# guitar_pedal_adapter.net
KiCad netlist of a schematic drawn in EAGLE
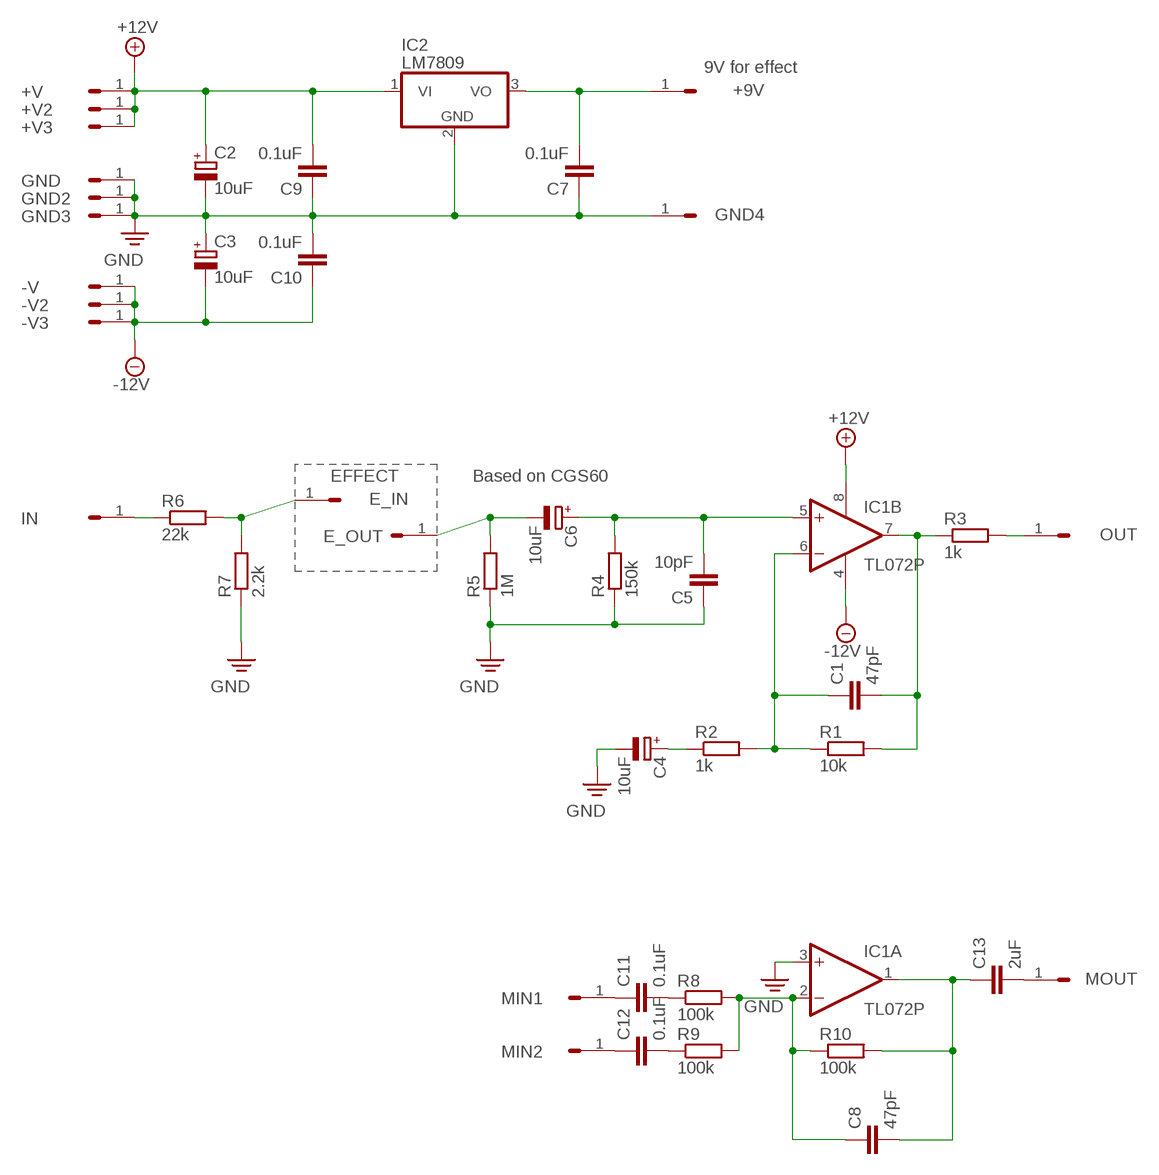
[diagram p0: schematic, sheet 1]

(export (version "E")
  (design (tool "Eeschema 10.0.6"))
  (components
    (comp (ref "+9V")
      (value "HEADER/MALE/01")
      (footprint "eagle-import:HEADER_MALE_01")
      (fields (field (name "SPICEPREFIX") "X"))
      (libsource (lib "eagle-import") (part "HEADER/MALE/01"))
    )
    (comp (ref "+V")
      (value "HEADER/MALE/01")
      (footprint "eagle-import:HEADER_MALE_01")
      (fields (field (name "SPICEPREFIX") "X"))
      (libsource (lib "eagle-import") (part "HEADER/MALE/01"))
    )
    (comp (ref "+V2")
      (value "HEADER/MALE/01")
      (footprint "eagle-import:HEADER_MALE_01")
      (fields (field (name "SPICEPREFIX") "X"))
      (libsource (lib "eagle-import") (part "HEADER/MALE/01"))
    )
    (comp (ref "+V3")
      (value "HEADER/MALE/01")
      (footprint "eagle-import:HEADER_MALE_01")
      (fields (field (name "SPICEPREFIX") "X"))
      (libsource (lib "eagle-import") (part "HEADER/MALE/01"))
    )
    (comp (ref "-V")
      (value "HEADER/MALE/01")
      (footprint "eagle-import:HEADER_MALE_01")
      (fields (field (name "SPICEPREFIX") "X"))
      (libsource (lib "eagle-import") (part "HEADER/MALE/01"))
    )
    (comp (ref "-V2")
      (value "HEADER/MALE/01")
      (footprint "eagle-import:HEADER_MALE_01")
      (fields (field (name "SPICEPREFIX") "X"))
      (libsource (lib "eagle-import") (part "HEADER/MALE/01"))
    )
    (comp (ref "-V3")
      (value "HEADER/MALE/01")
      (footprint "eagle-import:HEADER_MALE_01")
      (fields (field (name "SPICEPREFIX") "X"))
      (libsource (lib "eagle-import") (part "HEADER/MALE/01"))
    )
    (comp (ref "C1")
      (value "47pF")
      (footprint "eagle-import:CERAMICDISC_5")
      (libsource (lib "eagle-import") (part "CAPACITORCERAMICDISC/5"))
    )
    (comp (ref "C2")
      (value "10uF")
      (footprint "eagle-import:E2,5-6")
      (fields (field (name "SPICEPREFIX") "C"))
      (libsource (lib "eagle-import") (part "CAPACITOR/POLARIZEDE2.5-6"))
    )
    (comp (ref "C3")
      (value "10uF")
      (footprint "eagle-import:E2,5-6")
      (fields (field (name "SPICEPREFIX") "C"))
      (libsource (lib "eagle-import") (part "CAPACITOR/POLARIZEDE2.5-6"))
    )
    (comp (ref "C4")
      (value "10uF")
      (footprint "eagle-import:E2,5-6")
      (fields (field (name "SPICEPREFIX") "C"))
      (libsource (lib "eagle-import") (part "CAPACITOR/POLARIZEDE2.5-6"))
    )
    (comp (ref "C5")
      (value "10pF")
      (footprint "eagle-import:CERAMICDISC_5")
      (libsource (lib "eagle-import") (part "CAPACITORCERAMICDISC/5"))
    )
    (comp (ref "C6")
      (value "10uF")
      (footprint "eagle-import:E2,5-6")
      (fields (field (name "SPICEPREFIX") "C"))
      (libsource (lib "eagle-import") (part "CAPACITOR/POLARIZEDE2.5-6"))
    )
    (comp (ref "C7")
      (value "0.1uF")
      (footprint "eagle-import:CERAMICDISC_5")
      (libsource (lib "eagle-import") (part "CAPACITORCERAMICDISC/5"))
    )
    (comp (ref "C8")
      (value "47pF")
      (footprint "eagle-import:CERAMICDISC_5")
      (libsource (lib "eagle-import") (part "CAPACITORCERAMICDISC/5"))
    )
    (comp (ref "C9")
      (value "0.1uF")
      (footprint "eagle-import:CERAMICDISC_5")
      (libsource (lib "eagle-import") (part "CAPACITORCERAMICDISC/5"))
    )
    (comp (ref "C10")
      (value "0.1uF")
      (footprint "eagle-import:CERAMICDISC_5")
      (libsource (lib "eagle-import") (part "CAPACITORCERAMICDISC/5"))
    )
    (comp (ref "C11")
      (value "0.1uF")
      (footprint "eagle-import:CERAMICDISC_5")
      (libsource (lib "eagle-import") (part "CAPACITORCERAMICDISC/5"))
    )
    (comp (ref "C12")
      (value "0.1uF")
      (footprint "eagle-import:CERAMICDISC_5")
      (libsource (lib "eagle-import") (part "CAPACITORCERAMICDISC/5"))
    )
    (comp (ref "C13")
      (value "2uF")
      (footprint "eagle-import:CERAMICDISC_5")
      (libsource (lib "eagle-import") (part "CAPACITORCERAMICDISC/5"))
    )
    (comp (ref "E_IN")
      (value "HEADER/MALE/01")
      (footprint "eagle-import:HEADER_MALE_01")
      (fields (field (name "SPICEPREFIX") "X"))
      (libsource (lib "eagle-import") (part "HEADER/MALE/01"))
    )
    (comp (ref "E_OUT")
      (value "HEADER/MALE/01")
      (footprint "eagle-import:HEADER_MALE_01")
      (fields (field (name "SPICEPREFIX") "X"))
      (libsource (lib "eagle-import") (part "HEADER/MALE/01"))
    )
    (comp (ref "GND")
      (value "HEADER/MALE/01")
      (footprint "eagle-import:HEADER_MALE_01")
      (fields (field (name "SPICEPREFIX") "X"))
      (libsource (lib "eagle-import") (part "HEADER/MALE/01"))
    )
    (comp (ref "GND2")
      (value "HEADER/MALE/01")
      (footprint "eagle-import:HEADER_MALE_01")
      (fields (field (name "SPICEPREFIX") "X"))
      (libsource (lib "eagle-import") (part "HEADER/MALE/01"))
    )
    (comp (ref "GND3")
      (value "HEADER/MALE/01")
      (footprint "eagle-import:HEADER_MALE_01")
      (fields (field (name "SPICEPREFIX") "X"))
      (libsource (lib "eagle-import") (part "HEADER/MALE/01"))
    )
    (comp (ref "GND4")
      (value "HEADER/MALE/01")
      (footprint "eagle-import:HEADER_MALE_01")
      (fields (field (name "SPICEPREFIX") "X"))
      (libsource (lib "eagle-import") (part "HEADER/MALE/01"))
    )
    (comp (ref "IC1")
      (value "TL072P")
      (footprint "eagle-import:DIL08")
      (libsource (lib "eagle-import") (part "TL072P"))
    )
    (comp (ref "IC2")
      (value "LM7809")
      (footprint "eagle-import:TO220V")
      (libsource (lib "eagle-import") (part "78TV05"))
    )
    (comp (ref "IN")
      (value "HEADER/MALE/01")
      (footprint "eagle-import:HEADER_MALE_01")
      (fields (field (name "SPICEPREFIX") "X"))
      (libsource (lib "eagle-import") (part "HEADER/MALE/01"))
    )
    (comp (ref "MIN1")
      (value "HEADER/MALE/01")
      (footprint "eagle-import:HEADER_MALE_01")
      (fields (field (name "SPICEPREFIX") "X"))
      (libsource (lib "eagle-import") (part "HEADER/MALE/01"))
    )
    (comp (ref "MIN2")
      (value "HEADER/MALE/01")
      (footprint "eagle-import:HEADER_MALE_01")
      (fields (field (name "SPICEPREFIX") "X"))
      (libsource (lib "eagle-import") (part "HEADER/MALE/01"))
    )
    (comp (ref "MOUT")
      (value "HEADER/MALE/01")
      (footprint "eagle-import:HEADER_MALE_01")
      (fields (field (name "SPICEPREFIX") "X"))
      (libsource (lib "eagle-import") (part "HEADER/MALE/01"))
    )
    (comp (ref "OUT")
      (value "HEADER/MALE/01")
      (footprint "eagle-import:HEADER_MALE_01")
      (fields (field (name "SPICEPREFIX") "X"))
      (libsource (lib "eagle-import") (part "HEADER/MALE/01"))
    )
    (comp (ref "R1")
      (value "10k")
      (footprint "eagle-import:RESISTOR_7.5")
      (libsource (lib "eagle-import") (part "RESISTORRESISTOR/UPRIGHT/7.5"))
    )
    (comp (ref "R2")
      (value "1k")
      (footprint "eagle-import:RESISTOR_7.5")
      (libsource (lib "eagle-import") (part "RESISTORRESISTOR/UPRIGHT/7.5"))
    )
    (comp (ref "R3")
      (value "1k")
      (footprint "eagle-import:RESISTOR_7.5")
      (libsource (lib "eagle-import") (part "RESISTORRESISTOR/UPRIGHT/7.5"))
    )
    (comp (ref "R4")
      (value "150k")
      (footprint "eagle-import:RESISTOR_7.5")
      (libsource (lib "eagle-import") (part "RESISTORRESISTOR/UPRIGHT/7.5"))
    )
    (comp (ref "R5")
      (value "1M")
      (footprint "eagle-import:RESISTOR_7.5")
      (libsource (lib "eagle-import") (part "RESISTORRESISTOR/UPRIGHT/7.5"))
    )
    (comp (ref "R6")
      (value "22k")
      (footprint "eagle-import:RESISTOR_7.5")
      (libsource (lib "eagle-import") (part "RESISTORRESISTOR/UPRIGHT/7.5"))
    )
    (comp (ref "R7")
      (value "2.2k")
      (footprint "eagle-import:RESISTOR_7.5")
      (libsource (lib "eagle-import") (part "RESISTORRESISTOR/UPRIGHT/7.5"))
    )
    (comp (ref "R8")
      (value "100k")
      (footprint "eagle-import:RESISTOR_7.5")
      (libsource (lib "eagle-import") (part "RESISTORRESISTOR/UPRIGHT/7.5"))
    )
    (comp (ref "R9")
      (value "100k")
      (footprint "eagle-import:RESISTOR_7.5")
      (libsource (lib "eagle-import") (part "RESISTORRESISTOR/UPRIGHT/7.5"))
    )
    (comp (ref "R10")
      (value "100k")
      (footprint "eagle-import:RESISTOR_7.5")
      (libsource (lib "eagle-import") (part "RESISTORRESISTOR/UPRIGHT/7.5"))
    )
  )
  (nets
    (net (code "1") (name "+12V") (class "Default")
      (node (ref "+V") (pin "1") (pinfunction "3_1") (pintype "passive"))
      (node (ref "+V2") (pin "1") (pinfunction "3_1") (pintype "passive"))
      (node (ref "+V3") (pin "1") (pinfunction "3_1") (pintype "passive"))
      (node (ref "C2") (pin "+") (pinfunction "+_+") (pintype "passive"))
      (node (ref "C9") (pin "2") (pinfunction "2_2") (pintype "passive"))
      (node (ref "IC1") (pin "8") (pinfunction "V+_8") (pintype "power_in"))
      (node (ref "IC2") (pin "1") (pinfunction "VI_1") (pintype "input"))
    )
    (net (code "2") (name "-12V") (class "Default")
      (node (ref "-V") (pin "1") (pinfunction "3_1") (pintype "passive"))
      (node (ref "-V2") (pin "1") (pinfunction "3_1") (pintype "passive"))
      (node (ref "-V3") (pin "1") (pinfunction "3_1") (pintype "passive"))
      (node (ref "C10") (pin "1") (pinfunction "1_1") (pintype "passive"))
      (node (ref "C3") (pin "-") (pinfunction "-_-") (pintype "passive"))
      (node (ref "IC1") (pin "4") (pinfunction "V-_4") (pintype "power_in"))
    )
    (net (code "3") (name "GND") (class "Default")
      (node (ref "C10") (pin "2") (pinfunction "2_2") (pintype "passive"))
      (node (ref "C2") (pin "-") (pinfunction "-_-") (pintype "passive"))
      (node (ref "C3") (pin "+") (pinfunction "+_+") (pintype "passive"))
      (node (ref "C4") (pin "-") (pinfunction "-_-") (pintype "passive"))
      (node (ref "C5") (pin "1") (pinfunction "1_1") (pintype "passive"))
      (node (ref "C7") (pin "1") (pinfunction "1_1") (pintype "passive"))
      (node (ref "C9") (pin "1") (pinfunction "1_1") (pintype "passive"))
      (node (ref "GND") (pin "1") (pinfunction "3_1") (pintype "passive"))
      (node (ref "GND2") (pin "1") (pinfunction "3_1") (pintype "passive"))
      (node (ref "GND3") (pin "1") (pinfunction "3_1") (pintype "passive"))
      (node (ref "GND4") (pin "1") (pinfunction "3_1") (pintype "passive"))
      (node (ref "IC1") (pin "3") (pinfunction "+IN_3") (pintype "input"))
      (node (ref "IC2") (pin "2") (pinfunction "GND_2") (pintype "passive"))
      (node (ref "R4") (pin "1") (pinfunction "1_1") (pintype "passive"))
      (node (ref "R5") (pin "1") (pinfunction "1_1") (pintype "passive"))
      (node (ref "R7") (pin "1") (pinfunction "1_1") (pintype "passive"))
    )
    (net (code "4") (name "Net-(+9V-3)") (class "Default")
      (node (ref "+9V") (pin "1") (pinfunction "3_1") (pintype "passive"))
      (node (ref "C7") (pin "2") (pinfunction "2_2") (pintype "passive"))
      (node (ref "IC2") (pin "3") (pinfunction "VO_3") (pintype "passive"))
    )
    (net (code "5") (name "Net-(C4-Pad+)") (class "Default")
      (node (ref "C4") (pin "+") (pinfunction "+_+") (pintype "passive"))
      (node (ref "R2") (pin "1") (pinfunction "1_1") (pintype "passive"))
    )
    (net (code "6") (name "Net-(C11-Pad2)") (class "Default")
      (node (ref "C11") (pin "2") (pinfunction "2_2") (pintype "passive"))
      (node (ref "R8") (pin "1") (pinfunction "1_1") (pintype "passive"))
    )
    (net (code "7") (name "Net-(C12-Pad2)") (class "Default")
      (node (ref "C12") (pin "2") (pinfunction "2_2") (pintype "passive"))
      (node (ref "R9") (pin "1") (pinfunction "1_1") (pintype "passive"))
    )
    (net (code "8") (name "Net-(E_IN-3)") (class "Default")
      (node (ref "E_IN") (pin "1") (pinfunction "3_1") (pintype "passive"))
      (node (ref "R6") (pin "2") (pinfunction "2_2") (pintype "passive"))
      (node (ref "R7") (pin "2") (pinfunction "2_2") (pintype "passive"))
    )
    (net (code "9") (name "Net-(E_OUT-3)") (class "Default")
      (node (ref "C6") (pin "-") (pinfunction "-_-") (pintype "passive"))
      (node (ref "E_OUT") (pin "1") (pinfunction "3_1") (pintype "passive"))
      (node (ref "R5") (pin "2") (pinfunction "2_2") (pintype "passive"))
    )
    (net (code "10") (name "Net-(IC1A--IN)") (class "Default")
      (node (ref "C8") (pin "1") (pinfunction "1_1") (pintype "passive"))
      (node (ref "IC1") (pin "2") (pinfunction "-IN_2") (pintype "input"))
      (node (ref "R10") (pin "1") (pinfunction "1_1") (pintype "passive"))
      (node (ref "R8") (pin "2") (pinfunction "2_2") (pintype "passive"))
      (node (ref "R9") (pin "2") (pinfunction "2_2") (pintype "passive"))
    )
    (net (code "11") (name "Net-(IC1A-OUT)") (class "Default")
      (node (ref "C13") (pin "1") (pinfunction "1_1") (pintype "passive"))
      (node (ref "C8") (pin "2") (pinfunction "2_2") (pintype "passive"))
      (node (ref "IC1") (pin "1") (pinfunction "OUT_1") (pintype "output"))
      (node (ref "R10") (pin "2") (pinfunction "2_2") (pintype "passive"))
    )
    (net (code "12") (name "Net-(IC1B-+IN)") (class "Default")
      (node (ref "C5") (pin "2") (pinfunction "2_2") (pintype "passive"))
      (node (ref "C6") (pin "+") (pinfunction "+_+") (pintype "passive"))
      (node (ref "IC1") (pin "5") (pinfunction "+IN_5") (pintype "input"))
      (node (ref "R4") (pin "2") (pinfunction "2_2") (pintype "passive"))
    )
    (net (code "13") (name "Net-(IC1B--IN)") (class "Default")
      (node (ref "C1") (pin "1") (pinfunction "1_1") (pintype "passive"))
      (node (ref "IC1") (pin "6") (pinfunction "-IN_6") (pintype "input"))
      (node (ref "R1") (pin "1") (pinfunction "1_1") (pintype "passive"))
      (node (ref "R2") (pin "2") (pinfunction "2_2") (pintype "passive"))
    )
    (net (code "14") (name "Net-(IC1B-OUT)") (class "Default")
      (node (ref "C1") (pin "2") (pinfunction "2_2") (pintype "passive"))
      (node (ref "IC1") (pin "7") (pinfunction "OUT_7") (pintype "output"))
      (node (ref "R1") (pin "2") (pinfunction "2_2") (pintype "passive"))
      (node (ref "R3") (pin "1") (pinfunction "1_1") (pintype "passive"))
    )
    (net (code "15") (name "Net-(IN-3)") (class "Default")
      (node (ref "IN") (pin "1") (pinfunction "3_1") (pintype "passive"))
      (node (ref "R6") (pin "1") (pinfunction "1_1") (pintype "passive"))
    )
    (net (code "16") (name "Net-(MIN1-3)") (class "Default")
      (node (ref "C11") (pin "1") (pinfunction "1_1") (pintype "passive"))
      (node (ref "MIN1") (pin "1") (pinfunction "3_1") (pintype "passive"))
    )
    (net (code "17") (name "Net-(MIN2-3)") (class "Default")
      (node (ref "C12") (pin "1") (pinfunction "1_1") (pintype "passive"))
      (node (ref "MIN2") (pin "1") (pinfunction "3_1") (pintype "passive"))
    )
    (net (code "18") (name "Net-(MOUT-3)") (class "Default")
      (node (ref "C13") (pin "2") (pinfunction "2_2") (pintype "passive"))
      (node (ref "MOUT") (pin "1") (pinfunction "3_1") (pintype "passive"))
    )
    (net (code "19") (name "Net-(OUT-3)") (class "Default")
      (node (ref "OUT") (pin "1") (pinfunction "3_1") (pintype "passive"))
      (node (ref "R3") (pin "2") (pinfunction "2_2") (pintype "passive"))
    )
  )
)
